# design.net
KiCad netlist of a schematic drawn in Altium Designer
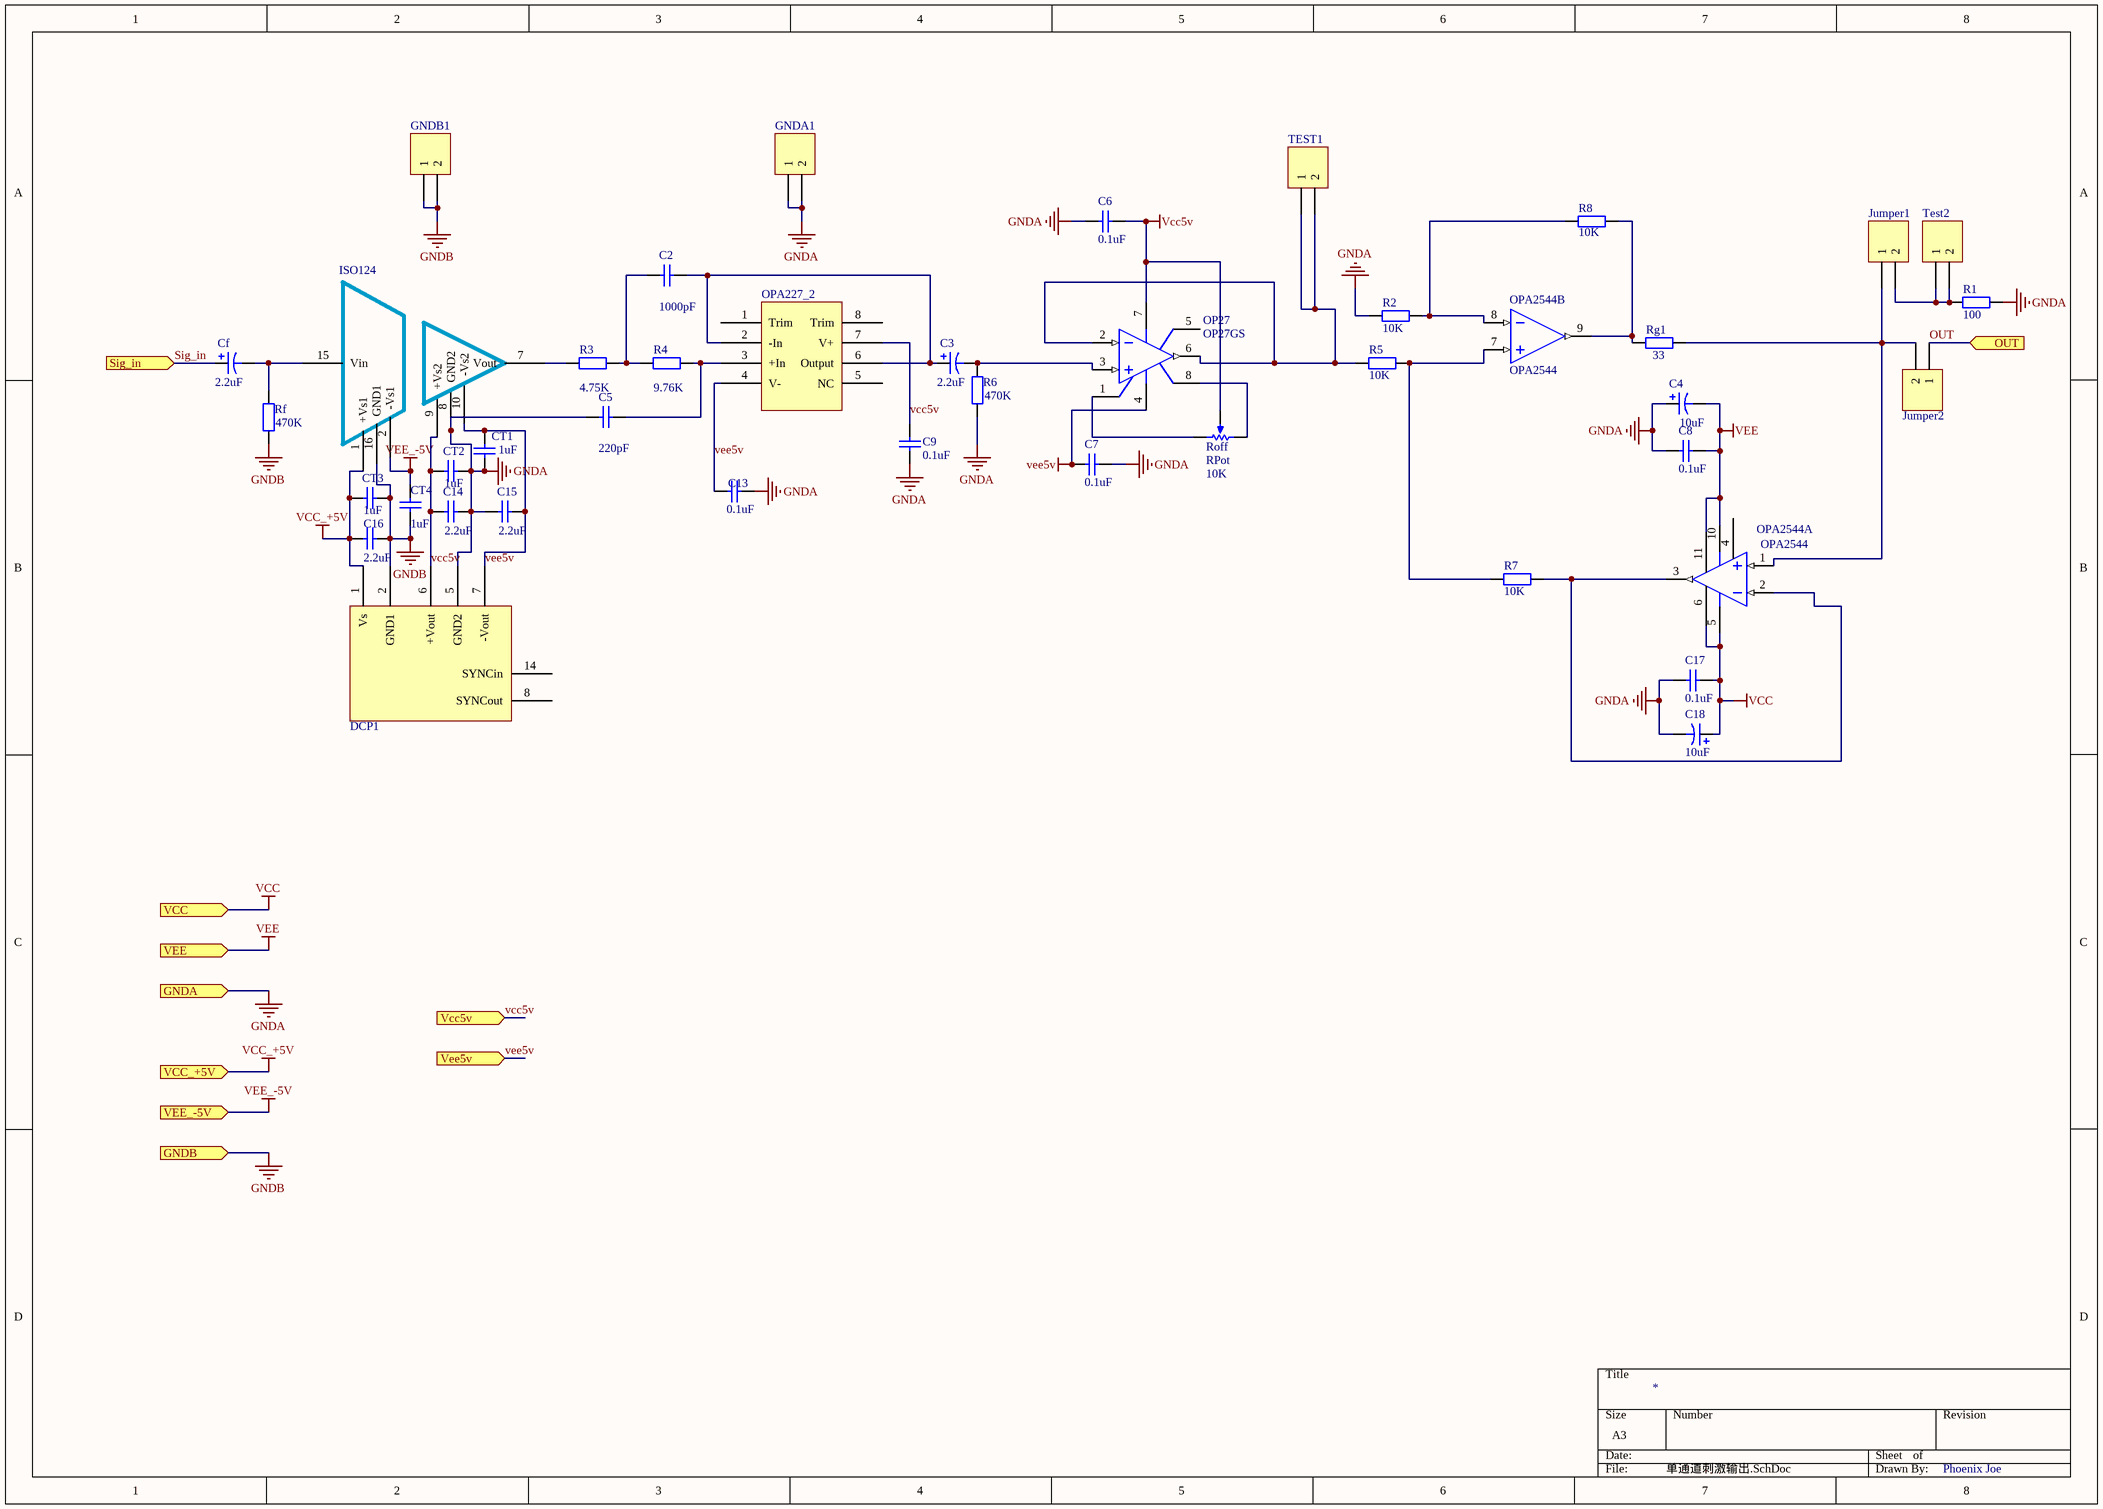
[diagram p0: 单通道刺激输出.SchDoc]

(export (version "E")
  (design (tool "Eeschema 10.0.6"))
  (components
    (comp (ref "C2")
      (value "1000pF")
      (footprint "cap0603")
      (description "Capacitor")
      (fields (field (name "Comment") "1000p") (field (name "PUBLISHER") "Altium Limited"))
      (libsource (lib "Miscellaneous Devices") (part "Cap"))
    )
    (comp (ref "C3")
      (value "2.2uF")
      (footprint "TAN_CAP-A")
      (description "Polarized Capacitor (Radial)")
      (fields (field (name "Comment") "2.2u") (field (name "PUBLISHER") "Altium Limited"))
      (libsource (lib "Miscellaneous Devices") (part "Cap Pol1"))
    )
    (comp (ref "C4")
      (value "10uF")
      (footprint "TAN_CAP-B")
      (description "Polarized Capacitor (Radial)")
      (fields (field (name "Comment") "10u") (field (name "PUBLISHER") "Altium Limited"))
      (libsource (lib "Miscellaneous Devices") (part "Cap Pol1"))
    )
    (comp (ref "C5")
      (value "220pF")
      (footprint "cap0603")
      (description "Capacitor")
      (fields (field (name "Comment") "220p") (field (name "PUBLISHER") "Altium Limited"))
      (libsource (lib "Miscellaneous Devices") (part "Cap"))
    )
    (comp (ref "C6")
      (value "0.1uF")
      (footprint "cap0603")
      (description "Capacitor")
      (fields (field (name "Comment") "0.1u") (field (name "PUBLISHER") "Altium Limited"))
      (libsource (lib "Miscellaneous Devices") (part "Cap"))
    )
    (comp (ref "C7")
      (value "0.1uF")
      (footprint "cap0603")
      (description "Capacitor")
      (fields (field (name "Comment") "0.1u") (field (name "PUBLISHER") "Altium Limited"))
      (libsource (lib "Miscellaneous Devices") (part "Cap"))
    )
    (comp (ref "C8")
      (value "0.1uF")
      (footprint "RAD-0.2")
      (description "Capacitor")
      (fields (field (name "Comment") "0.1u") (field (name "PUBLISHER") "Altium Limited"))
      (libsource (lib "Miscellaneous Devices") (part "Cap"))
    )
    (comp (ref "C9")
      (value "0.1uF")
      (footprint "cap0603")
      (description "Capacitor")
      (fields (field (name "Comment") "0.1u") (field (name "PUBLISHER") "Altium Limited"))
      (libsource (lib "Miscellaneous Devices") (part "Cap"))
    )
    (comp (ref "C13")
      (value "0.1uF")
      (footprint "cap0603")
      (description "Capacitor")
      (fields (field (name "Comment") "0.1u") (field (name "PUBLISHER") "Altium Limited"))
      (libsource (lib "Miscellaneous Devices") (part "Cap"))
    )
    (comp (ref "C14")
      (value "2.2uF")
      (footprint "cap0603")
      (description "Capacitor")
      (fields (field (name "Comment") "2.2u") (field (name "PUBLISHER") "Altium Limited"))
      (libsource (lib "Miscellaneous Devices") (part "Cap"))
    )
    (comp (ref "C15")
      (value "2.2uF")
      (footprint "cap0603")
      (description "Capacitor")
      (fields (field (name "Comment") "2.2u") (field (name "PUBLISHER") "Altium Limited"))
      (libsource (lib "Miscellaneous Devices") (part "Cap"))
    )
    (comp (ref "C16")
      (value "2.2uF")
      (footprint "cap0603")
      (description "Capacitor")
      (fields (field (name "Comment") "2.2u") (field (name "PUBLISHER") "Altium Limited"))
      (libsource (lib "Miscellaneous Devices") (part "Cap"))
    )
    (comp (ref "C17")
      (value "0.1uF")
      (footprint "RAD-0.2")
      (description "Capacitor")
      (fields (field (name "Comment") "0.1u") (field (name "PUBLISHER") "Altium Limited"))
      (libsource (lib "Miscellaneous Devices") (part "Cap"))
    )
    (comp (ref "C18")
      (value "10uF")
      (footprint "TAN_CAP-B")
      (description "Polarized Capacitor (Radial)")
      (fields (field (name "Comment") "10u") (field (name "PUBLISHER") "Altium Limited"))
      (libsource (lib "Miscellaneous Devices") (part "Cap Pol1"))
    )
    (comp (ref "Cf")
      (value "2.2uF")
      (footprint "TAN_CAP-A")
      (description "Polarized Capacitor (Radial)")
      (fields (field (name "Comment") "2.2u") (field (name "PUBLISHER") "Altium Limited"))
      (libsource (lib "Miscellaneous Devices") (part "Cap Pol1"))
    )
    (comp (ref "CT1")
      (value "1uF")
      (footprint "cap0603")
      (description "Capacitor")
      (fields (field (name "Comment") "1u") (field (name "PUBLISHER") "Altium Limited"))
      (libsource (lib "Miscellaneous Devices") (part "Cap"))
    )
    (comp (ref "CT2")
      (value "1uF")
      (footprint "cap0603")
      (description "Capacitor")
      (fields (field (name "Comment") "1u") (field (name "PUBLISHER") "Altium Limited"))
      (libsource (lib "Miscellaneous Devices") (part "Cap"))
    )
    (comp (ref "CT3")
      (value "1uF")
      (footprint "cap0603")
      (description "Capacitor")
      (fields (field (name "Comment") "1u") (field (name "PUBLISHER") "Altium Limited"))
      (libsource (lib "Miscellaneous Devices") (part "Cap"))
    )
    (comp (ref "CT4")
      (value "1uF")
      (footprint "cap0603")
      (description "Capacitor")
      (fields (field (name "Comment") "1u") (field (name "PUBLISHER") "Altium Limited"))
      (libsource (lib "Miscellaneous Devices") (part "Cap"))
    )
    (comp (ref "DCP1")
      (value "DCP010505DB")
      (footprint "DIP-14")
      (libsource (lib "8通道刺激仪") (part "DCP010505DB"))
    )
    (comp (ref "GNDA1")
      (value "Header 2")
      (footprint "HDR1X2")
      (description "Header, 2-Pin")
      (fields (field (name "PUBLISHER") "Altium Limited"))
      (libsource (lib "Miscellaneous Connectors") (part "Header 2"))
    )
    (comp (ref "GNDB1")
      (value "Header 2")
      (footprint "HDR1X2")
      (description "Header, 2-Pin")
      (fields (field (name "PUBLISHER") "Altium Limited"))
      (libsource (lib "Miscellaneous Connectors") (part "Header 2"))
    )
    (comp (ref "ISO124") (value "ISO124") (footprint "DIP-16") (libsource (lib "8通道刺激仪") (part "ISO124")))
    (comp (ref "Jumper1")
      (value "Header 2")
      (footprint "HDR1X2")
      (description "Header, 2-Pin")
      (fields (field (name "PUBLISHER") "Altium Limited"))
      (libsource (lib "Miscellaneous Connectors") (part "Header 2"))
    )
    (comp (ref "Jumper2")
      (value "Header 2")
      (footprint "HDR1X2")
      (description "Header, 2-Pin")
      (fields (field (name "PUBLISHER") "Altium Limited"))
      (libsource (lib "") (part "Header 2_1"))
    )
    (comp (ref "OP27")
      (value "OP27GS")
      (footprint "OPA227(D)")
      (description "Low-Noise, Precision Operational Amplifier")
      (fields (field (name "PUBLISHER") "Altium Limited"))
      (libsource (lib "AD Operational Amplifier") (part "OP27GS"))
    )
    (comp (ref "OPA227_2")
      (value "OPA227")
      (footprint "OPA227(D)")
      (libsource (lib "8通道刺激仪") (part "OPA227"))
    )
    (comp (ref "OPA2544") (value "OPA2544") (footprint "OPA2544") (libsource (lib "8通道刺激仪") (part "OPA2544")))
    (comp (ref "R1")
      (value "100")
      (footprint "RES0603")
      (description "Resistor")
      (fields (field (name "PUBLISHER") "Altium Limited"))
      (libsource (lib "Miscellaneous Devices") (part "Res2"))
    )
    (comp (ref "R2")
      (value "10K")
      (footprint "RES0603")
      (description "Resistor")
      (fields (field (name "Comment") "10k") (field (name "PUBLISHER") "Altium Limited"))
      (libsource (lib "Miscellaneous Devices") (part "Res2"))
    )
    (comp (ref "R3")
      (value "4.75K")
      (footprint "RES0603")
      (description "Resistor")
      (fields (field (name "Comment") "4.75k") (field (name "PUBLISHER") "Altium Limited"))
      (libsource (lib "Miscellaneous Devices") (part "Res2"))
    )
    (comp (ref "R4")
      (value "9.76K")
      (footprint "RES0603")
      (description "Resistor")
      (fields (field (name "Comment") "9.76k") (field (name "PUBLISHER") "Altium Limited"))
      (libsource (lib "Miscellaneous Devices") (part "Res2"))
    )
    (comp (ref "R5")
      (value "10K")
      (footprint "RES0603")
      (description "Resistor")
      (fields (field (name "Comment") "10k") (field (name "PUBLISHER") "Altium Limited"))
      (libsource (lib "Miscellaneous Devices") (part "Res2"))
    )
    (comp (ref "R6")
      (value "470K")
      (footprint "RES0603")
      (description "Resistor")
      (fields (field (name "Comment") "470k") (field (name "PUBLISHER") "Altium Limited"))
      (libsource (lib "") (part "Res2_2"))
    )
    (comp (ref "R7")
      (value "10K")
      (footprint "RES0603")
      (description "Resistor")
      (fields (field (name "Comment") "10k") (field (name "PUBLISHER") "Altium Limited"))
      (libsource (lib "Miscellaneous Devices") (part "Res2"))
    )
    (comp (ref "R8")
      (value "10K")
      (footprint "RES0603")
      (description "Resistor")
      (fields (field (name "Comment") "10k") (field (name "PUBLISHER") "Altium Limited"))
      (libsource (lib "") (part "Res2_1"))
    )
    (comp (ref "Rf")
      (value "470K")
      (footprint "RES0603")
      (description "Resistor")
      (fields (field (name "Comment") "470k") (field (name "PUBLISHER") "Altium Limited"))
      (libsource (lib "") (part "Res2_2"))
    )
    (comp (ref "Rg1")
      (value "33")
      (footprint "AXIAL-0.5")
      (description "Resistor")
      (fields (field (name "PUBLISHER") "Altium Limited"))
      (libsource (lib "Miscellaneous Devices") (part "Res2"))
    )
    (comp (ref "Roff")
      (value "RPot")
      (footprint "POT4MM-2")
      (description "Potentiometer")
      (fields (field (name "ALTIUM_VALUE") "10K") (field (name "PUBLISHER") "Altium Limited"))
      (libsource (lib "Miscellaneous Devices") (part "RPot"))
    )
    (comp (ref "TEST1")
      (value "Header 2")
      (footprint "HDR1X2")
      (description "Header, 2-Pin")
      (fields (field (name "PUBLISHER") "Altium Limited"))
      (libsource (lib "Miscellaneous Connectors") (part "Header 2"))
    )
    (comp (ref "Test2")
      (value "Header 2")
      (footprint "HDR1X2")
      (description "Header, 2-Pin")
      (fields (field (name "PUBLISHER") "Altium Limited"))
      (libsource (lib "Miscellaneous Connectors") (part "Header 2"))
    )
  )
  (nets
    (net (code "1") (name "/OUT") (class "Default")
      (node (ref "Jumper2") (pin "1") (pinfunction "1_1") (pintype "passive"))
    )
    (net (code "2") (name "/Sig_in") (class "Default")
      (node (ref "Cf") (pin "1") (pinfunction "1_1") (pintype "passive"))
    )
    (net (code "3") (name "GNDA") (class "Default")
      (node (ref "C13") (pin "1") (pinfunction "1_1") (pintype "passive"))
      (node (ref "C14") (pin "2") (pinfunction "2_2") (pintype "passive"))
      (node (ref "C15") (pin "1") (pinfunction "1_1") (pintype "passive"))
      (node (ref "C17") (pin "1") (pinfunction "1_1") (pintype "passive"))
      (node (ref "C18") (pin "2") (pinfunction "2_2") (pintype "passive"))
      (node (ref "C4") (pin "1") (pinfunction "1_1") (pintype "passive"))
      (node (ref "C5") (pin "2") (pinfunction "2_2") (pintype "passive"))
      (node (ref "C6") (pin "1") (pinfunction "1_1") (pintype "passive"))
      (node (ref "C7") (pin "1") (pinfunction "1_1") (pintype "passive"))
      (node (ref "C8") (pin "1") (pinfunction "1_1") (pintype "passive"))
      (node (ref "C9") (pin "1") (pinfunction "1_1") (pintype "passive"))
      (node (ref "CT1") (pin "1") (pinfunction "1_1") (pintype "passive"))
      (node (ref "CT2") (pin "2") (pinfunction "2_2") (pintype "passive"))
      (node (ref "DCP1") (pin "5") (pinfunction "GND2_5") (pintype "passive"))
      (node (ref "GNDA1") (pin "1") (pinfunction "1_1") (pintype "passive"))
      (node (ref "GNDA1") (pin "2") (pinfunction "2_2") (pintype "passive"))
      (node (ref "ISO124") (pin "8") (pinfunction "GND2_8") (pintype "passive"))
      (node (ref "R1") (pin "2") (pinfunction "2_2") (pintype "passive"))
      (node (ref "R2") (pin "1") (pinfunction "1_1") (pintype "passive"))
      (node (ref "R6") (pin "1") (pinfunction "1_1") (pintype "passive"))
    )
    (net (code "4") (name "GNDB") (class "Default")
      (node (ref "C16") (pin "2") (pinfunction "2_2") (pintype "passive"))
      (node (ref "CT3") (pin "2") (pinfunction "2_2") (pintype "passive"))
      (node (ref "CT4") (pin "1") (pinfunction "1_1") (pintype "passive"))
      (node (ref "DCP1") (pin "2") (pinfunction "GND1_2") (pintype "passive"))
      (node (ref "GNDB1") (pin "1") (pinfunction "1_1") (pintype "passive"))
      (node (ref "GNDB1") (pin "2") (pinfunction "2_2") (pintype "passive"))
      (node (ref "ISO124") (pin "16") (pinfunction "GND1_16") (pintype "passive"))
      (node (ref "Rf") (pin "1") (pinfunction "1_1") (pintype "passive"))
    )
    (net (code "5") (name "Net-(C2-Pad1)") (class "Default")
      (node (ref "C2") (pin "1") (pinfunction "1_1") (pintype "passive"))
      (node (ref "R3") (pin "2") (pinfunction "2_2") (pintype "passive"))
      (node (ref "R4") (pin "1") (pinfunction "1_1") (pintype "passive"))
    )
    (net (code "6") (name "Net-(ISO124-Vin)") (class "Default")
      (node (ref "Cf") (pin "2") (pinfunction "2_2") (pintype "passive"))
      (node (ref "ISO124") (pin "15") (pinfunction "Vin_15") (pintype "passive"))
      (node (ref "Rf") (pin "2") (pinfunction "2_2") (pintype "passive"))
    )
    (net (code "7") (name "Net-(ISO124-Vout)") (class "Default")
      (node (ref "ISO124") (pin "7") (pinfunction "Vout_7") (pintype "passive"))
      (node (ref "R3") (pin "1") (pinfunction "1_1") (pintype "passive"))
    )
    (net (code "8") (name "Net-(Jumper1-Pad2)") (class "Default")
      (node (ref "Jumper1") (pin "2") (pinfunction "2_2") (pintype "passive"))
      (node (ref "R1") (pin "1") (pinfunction "1_1") (pintype "passive"))
      (node (ref "Test2") (pin "1") (pinfunction "1_1") (pintype "passive"))
      (node (ref "Test2") (pin "2") (pinfunction "2_2") (pintype "passive"))
    )
    (net (code "9") (name "Net-(OP27-IN+)") (class "Default")
      (node (ref "C3") (pin "2") (pinfunction "2_2") (pintype "passive"))
      (node (ref "OP27") (pin "3") (pinfunction "IN+_3") (pintype "input"))
      (node (ref "R6") (pin "2") (pinfunction "2_2") (pintype "passive"))
    )
    (net (code "10") (name "Net-(OP27-IN-)") (class "Default")
      (node (ref "OP27") (pin "2") (pinfunction "IN-_2") (pintype "input"))
      (node (ref "OP27") (pin "6") (pinfunction "OUT_6") (pintype "output"))
      (node (ref "R5") (pin "1") (pinfunction "1_1") (pintype "passive"))
      (node (ref "TEST1") (pin "1") (pinfunction "1_1") (pintype "passive"))
      (node (ref "TEST1") (pin "2") (pinfunction "2_2") (pintype "passive"))
    )
    (net (code "11") (name "Net-(OPA227_2-+In)") (class "Default")
      (node (ref "C5") (pin "1") (pinfunction "1_1") (pintype "passive"))
      (node (ref "OPA227_2") (pin "3") (pinfunction "+In_3") (pintype "passive"))
      (node (ref "R4") (pin "2") (pinfunction "2_2") (pintype "passive"))
    )
    (net (code "12") (name "Net-(OPA227_2--In)") (class "Default")
      (node (ref "C2") (pin "2") (pinfunction "2_2") (pintype "passive"))
      (node (ref "C3") (pin "1") (pinfunction "1_1") (pintype "passive"))
      (node (ref "OPA227_2") (pin "2") (pinfunction "-In_2") (pintype "passive"))
      (node (ref "OPA227_2") (pin "6") (pinfunction "Output_6") (pintype "passive"))
    )
    (net (code "13") (name "Net-(OPA2544A-IN+)") (class "Default")
      (node (ref "Jumper1") (pin "1") (pinfunction "1_1") (pintype "passive"))
      (node (ref "Jumper2") (pin "2") (pinfunction "2_2") (pintype "passive"))
      (node (ref "OPA2544") (pin "1") (pinfunction "IN+_1") (pintype "input"))
      (node (ref "Rg1") (pin "2") (pinfunction "2_2") (pintype "passive"))
    )
    (net (code "14") (name "Net-(OPA2544A-IN-)") (class "Default")
      (node (ref "OPA2544") (pin "2") (pinfunction "IN-_2") (pintype "input"))
      (node (ref "OPA2544") (pin "3") (pinfunction "OUT_3") (pintype "output"))
      (node (ref "R7") (pin "2") (pinfunction "2_2") (pintype "passive"))
    )
    (net (code "15") (name "Net-(OPA2544B-IN+)") (class "Default")
      (node (ref "OPA2544") (pin "7") (pinfunction "IN+_7") (pintype "input"))
      (node (ref "R5") (pin "2") (pinfunction "2_2") (pintype "passive"))
      (node (ref "R7") (pin "1") (pinfunction "1_1") (pintype "passive"))
    )
    (net (code "16") (name "Net-(OPA2544B-IN-)") (class "Default")
      (node (ref "OPA2544") (pin "8") (pinfunction "IN-_8") (pintype "input"))
      (node (ref "R2") (pin "2") (pinfunction "2_2") (pintype "passive"))
      (node (ref "R8") (pin "2") (pinfunction "2_2") (pintype "passive"))
    )
    (net (code "17") (name "Net-(OPA2544B-OUT)") (class "Default")
      (node (ref "OPA2544") (pin "9") (pinfunction "OUT_9") (pintype "output"))
      (node (ref "R8") (pin "1") (pinfunction "1_1") (pintype "passive"))
      (node (ref "Rg1") (pin "1") (pinfunction "1_1") (pintype "passive"))
    )
    (net (code "18") (name "Net-(Roff-BOT)") (class "Default")
      (node (ref "OP27") (pin "1") (pinfunction "CMPEN_1") (pintype "passive"))
      (node (ref "Roff") (pin "ccw") (pinfunction "BOT_ccw") (pintype "passive"))
    )
    (net (code "19") (name "Net-(Roff-TOP)") (class "Default")
      (node (ref "OP27") (pin "8") (pinfunction "CMPEN_8") (pintype "passive"))
      (node (ref "Roff") (pin "cw") (pinfunction "TOP_cw") (pintype "passive"))
    )
    (net (code "20") (name "VCC") (class "Default")
      (node (ref "C17") (pin "2") (pinfunction "2_2") (pintype "passive"))
      (node (ref "C18") (pin "1") (pinfunction "1_1") (pintype "passive"))
      (node (ref "OPA2544") (pin "5") (pinfunction "V+_5") (pintype "power_in"))
      (node (ref "OPA2544") (pin "6") (pinfunction "V+_6") (pintype "passive"))
    )
    (net (code "21") (name "VCC_+5V") (class "Default")
      (node (ref "C16") (pin "1") (pinfunction "1_1") (pintype "passive"))
      (node (ref "CT3") (pin "1") (pinfunction "1_1") (pintype "passive"))
      (node (ref "DCP1") (pin "1") (pinfunction "Vs_1") (pintype "passive"))
      (node (ref "ISO124") (pin "1") (pinfunction "+Vs1_1") (pintype "passive"))
    )
    (net (code "22") (name "VEE") (class "Default")
      (node (ref "C4") (pin "2") (pinfunction "2_2") (pintype "passive"))
      (node (ref "C8") (pin "2") (pinfunction "2_2") (pintype "passive"))
      (node (ref "OPA2544") (pin "10") (pinfunction "V-_10") (pintype "power_in"))
      (node (ref "OPA2544") (pin "11") (pinfunction "V-_11") (pintype "passive"))
    )
    (net (code "23") (name "VEE_-5V") (class "Default")
      (node (ref "CT4") (pin "2") (pinfunction "2_2") (pintype "passive"))
      (node (ref "ISO124") (pin "2") (pinfunction "-Vs1_2") (pintype "passive"))
    )
    (net (code "24") (name "Vcc5v") (class "Default")
      (node (ref "C14") (pin "1") (pinfunction "1_1") (pintype "passive"))
      (node (ref "C6") (pin "2") (pinfunction "2_2") (pintype "passive"))
      (node (ref "C9") (pin "2") (pinfunction "2_2") (pintype "passive"))
      (node (ref "CT2") (pin "1") (pinfunction "1_1") (pintype "passive"))
      (node (ref "DCP1") (pin "6") (pinfunction "+Vout_6") (pintype "passive"))
      (node (ref "ISO124") (pin "9") (pinfunction "+Vs2_9") (pintype "passive"))
      (node (ref "OP27") (pin "7") (pinfunction "V+_7") (pintype "power_in"))
      (node (ref "OPA227_2") (pin "7") (pinfunction "V+_7") (pintype "passive"))
      (node (ref "Roff") (pin "w") (pinfunction "TAP_w") (pintype "passive"))
    )
    (net (code "25") (name "unconnected-(DCP1-SYNCin-Pad14)") (class "Default")
      (node (ref "DCP1") (pin "14") (pinfunction "SYNCin_14") (pintype "passive"))
    )
    (net (code "26") (name "unconnected-(DCP1-SYNCout-Pad8)") (class "Default")
      (node (ref "DCP1") (pin "8") (pinfunction "SYNCout_8") (pintype "passive"))
    )
    (net (code "27") (name "unconnected-(OP27-NC-Pad5)") (class "Default")
      (node (ref "OP27") (pin "5") (pinfunction "NC_5") (pintype "passive"))
    )
    (net (code "28") (name "unconnected-(OPA227_2-NC-Pad5)") (class "Default")
      (node (ref "OPA227_2") (pin "5") (pinfunction "NC_5") (pintype "passive"))
    )
    (net (code "29") (name "unconnected-(OPA227_2-Trim-Pad1)") (class "Default")
      (node (ref "OPA227_2") (pin "1") (pinfunction "Trim_1") (pintype "passive"))
    )
    (net (code "30") (name "unconnected-(OPA227_2-Trim-Pad8)") (class "Default")
      (node (ref "OPA227_2") (pin "8") (pinfunction "Trim_8") (pintype "passive"))
    )
    (net (code "31") (name "unconnected-(OPA2544A-NC-Pad4)") (class "Default")
      (node (ref "OPA2544") (pin "4") (pinfunction "NC_4") (pintype "passive"))
    )
    (net (code "32") (name "vee5v") (class "Default")
      (node (ref "C13") (pin "2") (pinfunction "2_2") (pintype "passive"))
      (node (ref "C15") (pin "2") (pinfunction "2_2") (pintype "passive"))
      (node (ref "C7") (pin "2") (pinfunction "2_2") (pintype "passive"))
      (node (ref "CT1") (pin "2") (pinfunction "2_2") (pintype "passive"))
      (node (ref "DCP1") (pin "7") (pinfunction "-Vout_7") (pintype "passive"))
      (node (ref "ISO124") (pin "10") (pinfunction "-Vs2_10") (pintype "passive"))
      (node (ref "OP27") (pin "4") (pinfunction "V-_4") (pintype "power_in"))
      (node (ref "OPA227_2") (pin "4") (pinfunction "V-_4") (pintype "passive"))
    )
  )
)
